# shades_v40.net
KiCad netlist of a schematic drawn in EAGLE
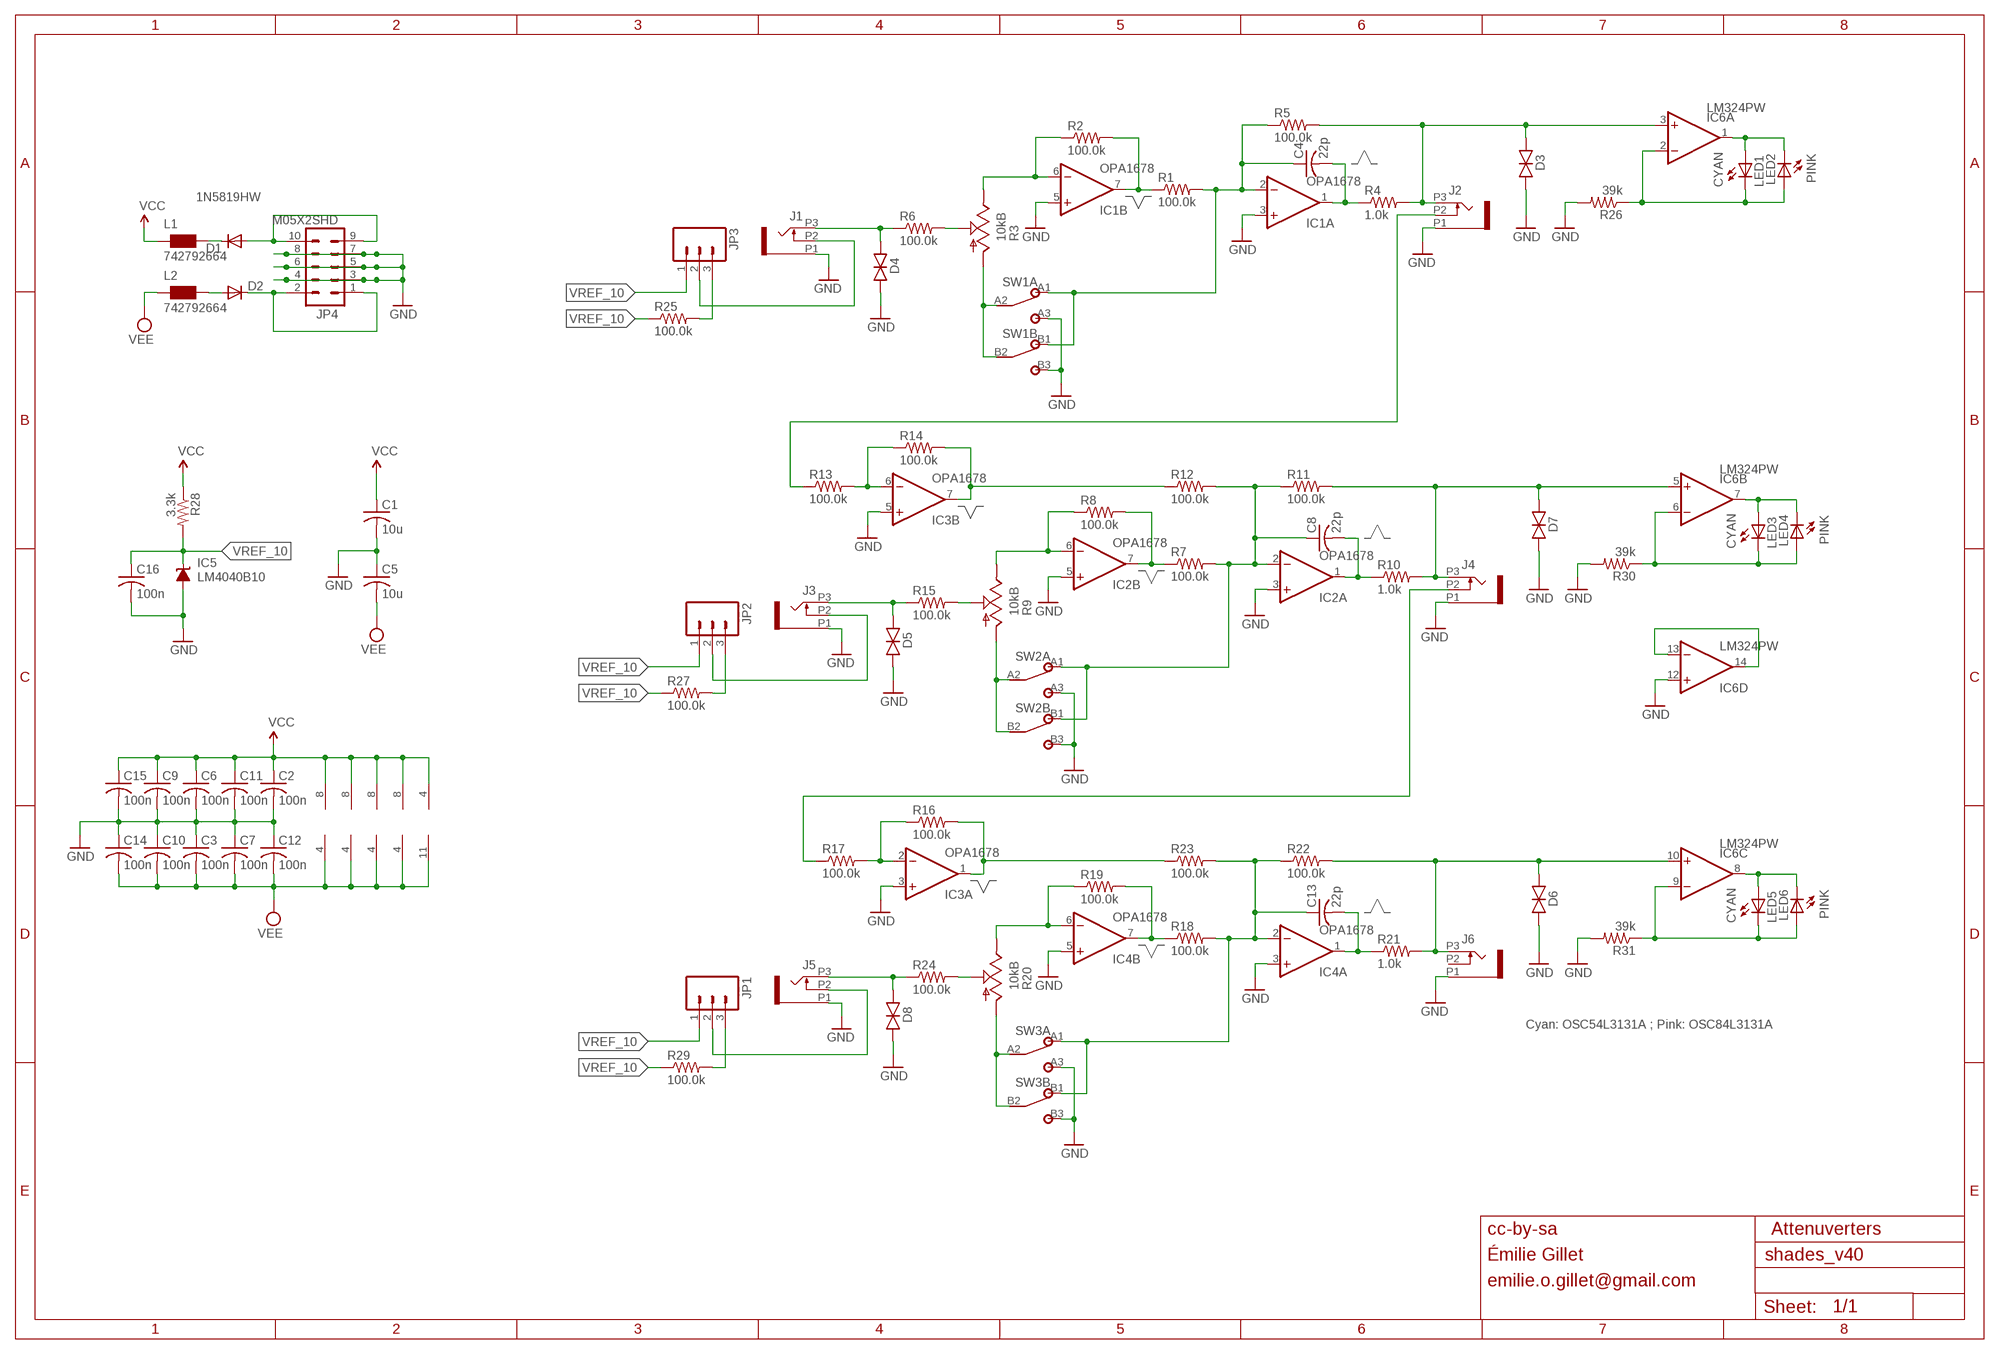
[diagram p0: schematic, sheet 1]

(export (version "E")
  (design (tool "Eeschema 10.0.6"))
  (components
    (comp (ref "C1")
      (value "10u")
      (footprint "eagle-import:C1210")
      (libsource (lib "eagle-import") (part "C-USC1210"))
    )
    (comp (ref "C2")
      (value "100n")
      (footprint "eagle-import:C0402")
      (libsource (lib "eagle-import") (part "C-USC0402"))
    )
    (comp (ref "C3")
      (value "100n")
      (footprint "eagle-import:C0402")
      (libsource (lib "eagle-import") (part "C-USC0402"))
    )
    (comp (ref "C4")
      (value "22p")
      (footprint "eagle-import:C0402")
      (libsource (lib "eagle-import") (part "C-USC0402"))
    )
    (comp (ref "C5")
      (value "10u")
      (footprint "eagle-import:C1210")
      (libsource (lib "eagle-import") (part "C-USC1210"))
    )
    (comp (ref "C6")
      (value "100n")
      (footprint "eagle-import:C0402")
      (libsource (lib "eagle-import") (part "C-USC0402"))
    )
    (comp (ref "C7")
      (value "100n")
      (footprint "eagle-import:C0402")
      (libsource (lib "eagle-import") (part "C-USC0402"))
    )
    (comp (ref "C8")
      (value "22p")
      (footprint "eagle-import:C0402")
      (libsource (lib "eagle-import") (part "C-USC0402"))
    )
    (comp (ref "C9")
      (value "100n")
      (footprint "eagle-import:C0402")
      (libsource (lib "eagle-import") (part "C-USC0402"))
    )
    (comp (ref "C10")
      (value "100n")
      (footprint "eagle-import:C0402")
      (libsource (lib "eagle-import") (part "C-USC0402"))
    )
    (comp (ref "C11")
      (value "100n")
      (footprint "eagle-import:C0402")
      (libsource (lib "eagle-import") (part "C-USC0402"))
    )
    (comp (ref "C12")
      (value "100n")
      (footprint "eagle-import:C0402")
      (libsource (lib "eagle-import") (part "C-USC0402"))
    )
    (comp (ref "C13")
      (value "22p")
      (footprint "eagle-import:C0402")
      (libsource (lib "eagle-import") (part "C-USC0402"))
    )
    (comp (ref "C14")
      (value "100n")
      (footprint "eagle-import:C0402")
      (libsource (lib "eagle-import") (part "C-USC0402"))
    )
    (comp (ref "C15")
      (value "100n")
      (footprint "eagle-import:C0402")
      (libsource (lib "eagle-import") (part "C-USC0402"))
    )
    (comp (ref "C16")
      (value "100n")
      (footprint "eagle-import:C0402")
      (libsource (lib "eagle-import") (part "C-USC0402"))
    )
    (comp (ref "D1")
      (value "1N5819HW")
      (footprint "eagle-import:SOD123")
      (libsource (lib "eagle-import") (part "DIODE-SOD123"))
    )
    (comp (ref "D2")
      (value "1N5819HW")
      (footprint "eagle-import:SOD123")
      (libsource (lib "eagle-import") (part "DIODE-SOD123"))
    )
    (comp (ref "D3")
      (value "TVS")
      (footprint "eagle-import:0603")
      (libsource (lib "eagle-import") (part "TVS"))
    )
    (comp (ref "D4")
      (value "TVS")
      (footprint "eagle-import:0603")
      (libsource (lib "eagle-import") (part "TVS"))
    )
    (comp (ref "D5")
      (value "TVS")
      (footprint "eagle-import:0603")
      (libsource (lib "eagle-import") (part "TVS"))
    )
    (comp (ref "D6")
      (value "TVS")
      (footprint "eagle-import:0603")
      (libsource (lib "eagle-import") (part "TVS"))
    )
    (comp (ref "D7")
      (value "TVS")
      (footprint "eagle-import:0603")
      (libsource (lib "eagle-import") (part "TVS"))
    )
    (comp (ref "D8")
      (value "TVS")
      (footprint "eagle-import:0603")
      (libsource (lib "eagle-import") (part "TVS"))
    )
    (comp (ref "IC1")
      (value "OPA1678")
      (footprint "eagle-import:VSSOP8")
      (libsource (lib "eagle-import") (part "OPA1678DGK"))
    )
    (comp (ref "IC2")
      (value "OPA1678")
      (footprint "eagle-import:VSSOP8")
      (libsource (lib "eagle-import") (part "OPA1678DGK"))
    )
    (comp (ref "IC3")
      (value "OPA1678")
      (footprint "eagle-import:VSSOP8")
      (libsource (lib "eagle-import") (part "OPA1678DGK"))
    )
    (comp (ref "IC4")
      (value "OPA1678")
      (footprint "eagle-import:VSSOP8")
      (libsource (lib "eagle-import") (part "OPA1678DGK"))
    )
    (comp (ref "IC5")
      (value "LM4040B10")
      (footprint "eagle-import:DBZ_R-PDSO-G3")
      (libsource (lib "eagle-import") (part "LM4041DBZB12"))
    )
    (comp (ref "IC6")
      (value "LM324PW")
      (footprint "eagle-import:TSSOP14_065")
      (libsource (lib "eagle-import") (part "TL074PW"))
    )
    (comp (ref "J1")
      (value "PJ301_THONKICONNTME")
      (footprint "eagle-import:WQP_PJ_301M_TME")
      (libsource (lib "eagle-import") (part "PJ301_THONKICONNTME"))
    )
    (comp (ref "J2")
      (value "PJ301_THONKICONNTME")
      (footprint "eagle-import:WQP_PJ_301M_TME")
      (libsource (lib "eagle-import") (part "PJ301_THONKICONNTME"))
    )
    (comp (ref "J3")
      (value "PJ301_THONKICONNTME")
      (footprint "eagle-import:WQP_PJ_301M_TME")
      (libsource (lib "eagle-import") (part "PJ301_THONKICONNTME"))
    )
    (comp (ref "J4")
      (value "PJ301_THONKICONNTME")
      (footprint "eagle-import:WQP_PJ_301M_TME")
      (libsource (lib "eagle-import") (part "PJ301_THONKICONNTME"))
    )
    (comp (ref "J5")
      (value "PJ301_THONKICONNTME")
      (footprint "eagle-import:WQP_PJ_301M_TME")
      (libsource (lib "eagle-import") (part "PJ301_THONKICONNTME"))
    )
    (comp (ref "J6")
      (value "PJ301_THONKICONNTME")
      (footprint "eagle-import:WQP_PJ_301M_TME")
      (libsource (lib "eagle-import") (part "PJ301_THONKICONNTME"))
    )
    (comp (ref "JP1")
      (value "M03PTH")
      (footprint "eagle-import:1X03")
      (libsource (lib "eagle-import") (part "M03PTH"))
    )
    (comp (ref "JP2")
      (value "M03PTH")
      (footprint "eagle-import:1X03")
      (libsource (lib "eagle-import") (part "M03PTH"))
    )
    (comp (ref "JP3")
      (value "M03PTH")
      (footprint "eagle-import:1X03")
      (libsource (lib "eagle-import") (part "M03PTH"))
    )
    (comp (ref "JP4")
      (value "M05X2SHD")
      (footprint "eagle-import:2X5-SHROUDED")
      (libsource (lib "eagle-import") (part "M05X2SHD"))
    )
    (comp (ref "L1")
      (value "742792664")
      (footprint "eagle-import:0603")
      (libsource (lib "eagle-import") (part "WE-CBF_0603"))
    )
    (comp (ref "L2")
      (value "742792664")
      (footprint "eagle-import:0603")
      (libsource (lib "eagle-import") (part "WE-CBF_0603"))
    )
    (comp (ref "LED1")
      (value "CYAN")
      (footprint "eagle-import:LED3MM")
      (libsource (lib "eagle-import") (part "LED3MM"))
    )
    (comp (ref "LED2")
      (value "PINK")
      (footprint "eagle-import:LED3MM")
      (libsource (lib "eagle-import") (part "LED3MM"))
    )
    (comp (ref "LED3")
      (value "CYAN")
      (footprint "eagle-import:LED3MM")
      (libsource (lib "eagle-import") (part "LED3MM"))
    )
    (comp (ref "LED4")
      (value "PINK")
      (footprint "eagle-import:LED3MM")
      (libsource (lib "eagle-import") (part "LED3MM"))
    )
    (comp (ref "LED5")
      (value "CYAN")
      (footprint "eagle-import:LED3MM")
      (libsource (lib "eagle-import") (part "LED3MM"))
    )
    (comp (ref "LED6")
      (value "PINK")
      (footprint "eagle-import:LED3MM")
      (libsource (lib "eagle-import") (part "LED3MM"))
    )
    (comp (ref "R1")
      (value "100.0k")
      (footprint "eagle-import:R0402")
      (libsource (lib "eagle-import") (part "R-US_R0402"))
    )
    (comp (ref "R2")
      (value "100.0k")
      (footprint "eagle-import:R0402")
      (libsource (lib "eagle-import") (part "R-US_R0402"))
    )
    (comp (ref "R3")
      (value "10kB")
      (footprint "eagle-import:ALPS_POT_VERTICAL_PS")
      (libsource (lib "eagle-import") (part "POT_USVERTICAL_PS"))
    )
    (comp (ref "R4")
      (value "1.0k")
      (footprint "eagle-import:R0603")
      (libsource (lib "eagle-import") (part "R-US_R0603"))
    )
    (comp (ref "R5")
      (value "100.0k")
      (footprint "eagle-import:R0402")
      (libsource (lib "eagle-import") (part "R-US_R0402"))
    )
    (comp (ref "R6")
      (value "100.0k")
      (footprint "eagle-import:R0402")
      (libsource (lib "eagle-import") (part "R-US_R0402"))
    )
    (comp (ref "R7")
      (value "100.0k")
      (footprint "eagle-import:R0402")
      (libsource (lib "eagle-import") (part "R-US_R0402"))
    )
    (comp (ref "R8")
      (value "100.0k")
      (footprint "eagle-import:R0402")
      (libsource (lib "eagle-import") (part "R-US_R0402"))
    )
    (comp (ref "R9")
      (value "10kB")
      (footprint "eagle-import:ALPS_POT_VERTICAL_PS")
      (libsource (lib "eagle-import") (part "POT_USVERTICAL_PS"))
    )
    (comp (ref "R10")
      (value "1.0k")
      (footprint "eagle-import:R0603")
      (libsource (lib "eagle-import") (part "R-US_R0603"))
    )
    (comp (ref "R11")
      (value "100.0k")
      (footprint "eagle-import:R0402")
      (libsource (lib "eagle-import") (part "R-US_R0402"))
    )
    (comp (ref "R12")
      (value "100.0k")
      (footprint "eagle-import:R0402")
      (libsource (lib "eagle-import") (part "R-US_R0402"))
    )
    (comp (ref "R13")
      (value "100.0k")
      (footprint "eagle-import:R0402")
      (libsource (lib "eagle-import") (part "R-US_R0402"))
    )
    (comp (ref "R14")
      (value "100.0k")
      (footprint "eagle-import:R0402")
      (libsource (lib "eagle-import") (part "R-US_R0402"))
    )
    (comp (ref "R15")
      (value "100.0k")
      (footprint "eagle-import:R0402")
      (libsource (lib "eagle-import") (part "R-US_R0402"))
    )
    (comp (ref "R16")
      (value "100.0k")
      (footprint "eagle-import:R0402")
      (libsource (lib "eagle-import") (part "R-US_R0402"))
    )
    (comp (ref "R17")
      (value "100.0k")
      (footprint "eagle-import:R0402")
      (libsource (lib "eagle-import") (part "R-US_R0402"))
    )
    (comp (ref "R18")
      (value "100.0k")
      (footprint "eagle-import:R0402")
      (libsource (lib "eagle-import") (part "R-US_R0402"))
    )
    (comp (ref "R19")
      (value "100.0k")
      (footprint "eagle-import:R0402")
      (libsource (lib "eagle-import") (part "R-US_R0402"))
    )
    (comp (ref "R20")
      (value "10kB")
      (footprint "eagle-import:ALPS_POT_VERTICAL_PS")
      (libsource (lib "eagle-import") (part "POT_USVERTICAL_PS"))
    )
    (comp (ref "R21")
      (value "1.0k")
      (footprint "eagle-import:R0603")
      (libsource (lib "eagle-import") (part "R-US_R0603"))
    )
    (comp (ref "R22")
      (value "100.0k")
      (footprint "eagle-import:R0402")
      (libsource (lib "eagle-import") (part "R-US_R0402"))
    )
    (comp (ref "R23")
      (value "100.0k")
      (footprint "eagle-import:R0402")
      (libsource (lib "eagle-import") (part "R-US_R0402"))
    )
    (comp (ref "R24")
      (value "100.0k")
      (footprint "eagle-import:R0402")
      (libsource (lib "eagle-import") (part "R-US_R0402"))
    )
    (comp (ref "R25")
      (value "100.0k")
      (footprint "eagle-import:R0402")
      (libsource (lib "eagle-import") (part "R-US_R0402"))
    )
    (comp (ref "R26")
      (value "39k")
      (footprint "eagle-import:R0402")
      (libsource (lib "eagle-import") (part "R-US_R0402"))
    )
    (comp (ref "R27")
      (value "100.0k")
      (footprint "eagle-import:R0402")
      (libsource (lib "eagle-import") (part "R-US_R0402"))
    )
    (comp (ref "R28")
      (value "3.3k")
      (footprint "eagle-import:R0402")
      (libsource (lib "eagle-import") (part "resistor_R-US_R0402"))
    )
    (comp (ref "R29")
      (value "100.0k")
      (footprint "eagle-import:R0402")
      (libsource (lib "eagle-import") (part "R-US_R0402"))
    )
    (comp (ref "R30")
      (value "39k")
      (footprint "eagle-import:R0402")
      (libsource (lib "eagle-import") (part "R-US_R0402"))
    )
    (comp (ref "R31")
      (value "39k")
      (footprint "eagle-import:R0402")
      (libsource (lib "eagle-import") (part "R-US_R0402"))
    )
    (comp (ref "SW1")
      (value "S-ON-ON-ONSS70070F-0202")
      (footprint "eagle-import:SS70070F-0202")
      (libsource (lib "eagle-import") (part "S-ON-ON-ONSS70070F-0202"))
    )
    (comp (ref "SW2")
      (value "S-ON-ON-ONSS70070F-0202")
      (footprint "eagle-import:SS70070F-0202")
      (libsource (lib "eagle-import") (part "S-ON-ON-ONSS70070F-0202"))
    )
    (comp (ref "SW3")
      (value "S-ON-ON-ONSS70070F-0202")
      (footprint "eagle-import:SS70070F-0202")
      (libsource (lib "eagle-import") (part "S-ON-ON-ONSS70070F-0202"))
    )
  )
  (nets
    (net (code "1") (name "GND") (class "Default")
      (node (ref "C1") (pin "2") (pinfunction "2_2") (pintype "passive"))
      (node (ref "C10") (pin "1") (pinfunction "1_1") (pintype "passive"))
      (node (ref "C11") (pin "2") (pinfunction "2_2") (pintype "passive"))
      (node (ref "C12") (pin "1") (pinfunction "1_1") (pintype "passive"))
      (node (ref "C14") (pin "1") (pinfunction "1_1") (pintype "passive"))
      (node (ref "C15") (pin "2") (pinfunction "2_2") (pintype "passive"))
      (node (ref "C16") (pin "2") (pinfunction "2_2") (pintype "passive"))
      (node (ref "C2") (pin "2") (pinfunction "2_2") (pintype "passive"))
      (node (ref "C3") (pin "1") (pinfunction "1_1") (pintype "passive"))
      (node (ref "C5") (pin "1") (pinfunction "1_1") (pintype "passive"))
      (node (ref "C6") (pin "2") (pinfunction "2_2") (pintype "passive"))
      (node (ref "C7") (pin "1") (pinfunction "1_1") (pintype "passive"))
      (node (ref "C9") (pin "2") (pinfunction "2_2") (pintype "passive"))
      (node (ref "D3") (pin "1") (pinfunction "A_1") (pintype "passive"))
      (node (ref "D4") (pin "1") (pinfunction "A_1") (pintype "passive"))
      (node (ref "D5") (pin "1") (pinfunction "A_1") (pintype "passive"))
      (node (ref "D6") (pin "1") (pinfunction "A_1") (pintype "passive"))
      (node (ref "D7") (pin "1") (pinfunction "A_1") (pintype "passive"))
      (node (ref "D8") (pin "1") (pinfunction "A_1") (pintype "passive"))
      (node (ref "IC1") (pin "3") (pinfunction "+IN_3") (pintype "input"))
      (node (ref "IC1") (pin "5") (pinfunction "+IN_5") (pintype "input"))
      (node (ref "IC2") (pin "3") (pinfunction "+IN_3") (pintype "input"))
      (node (ref "IC2") (pin "5") (pinfunction "+IN_5") (pintype "input"))
      (node (ref "IC3") (pin "3") (pinfunction "+IN_3") (pintype "input"))
      (node (ref "IC3") (pin "5") (pinfunction "+IN_5") (pintype "input"))
      (node (ref "IC4") (pin "3") (pinfunction "+IN_3") (pintype "input"))
      (node (ref "IC4") (pin "5") (pinfunction "+IN_5") (pintype "input"))
      (node (ref "IC5") (pin "2") (pinfunction "A_2") (pintype "passive"))
      (node (ref "IC6") (pin "12") (pinfunction "+IN_12") (pintype "input"))
      (node (ref "J1") (pin "P1") (pinfunction "1_P1") (pintype "passive"))
      (node (ref "J2") (pin "P1") (pinfunction "1_P1") (pintype "passive"))
      (node (ref "J3") (pin "P1") (pinfunction "1_P1") (pintype "passive"))
      (node (ref "J4") (pin "P1") (pinfunction "1_P1") (pintype "passive"))
      (node (ref "J5") (pin "P1") (pinfunction "1_P1") (pintype "passive"))
      (node (ref "J6") (pin "P1") (pinfunction "1_P1") (pintype "passive"))
      (node (ref "JP4") (pin "3") (pinfunction "3_3") (pintype "passive"))
      (node (ref "JP4") (pin "4") (pinfunction "4_4") (pintype "passive"))
      (node (ref "JP4") (pin "5") (pinfunction "5_5") (pintype "passive"))
      (node (ref "JP4") (pin "6") (pinfunction "6_6") (pintype "passive"))
      (node (ref "JP4") (pin "7") (pinfunction "7_7") (pintype "passive"))
      (node (ref "JP4") (pin "8") (pinfunction "8_8") (pintype "passive"))
      (node (ref "R26") (pin "2") (pinfunction "2_2") (pintype "passive"))
      (node (ref "R30") (pin "2") (pinfunction "2_2") (pintype "passive"))
      (node (ref "R31") (pin "2") (pinfunction "2_2") (pintype "passive"))
      (node (ref "SW1") (pin "A3") (pinfunction "3_A3") (pintype "passive"))
      (node (ref "SW1") (pin "B3") (pinfunction "3_B3") (pintype "passive"))
      (node (ref "SW2") (pin "A3") (pinfunction "3_A3") (pintype "passive"))
      (node (ref "SW2") (pin "B3") (pinfunction "3_B3") (pintype "passive"))
      (node (ref "SW3") (pin "A3") (pinfunction "3_A3") (pintype "passive"))
      (node (ref "SW3") (pin "B3") (pinfunction "3_B3") (pintype "passive"))
    )
    (net (code "2") (name "Net-(D1-PadA)") (class "Default")
      (node (ref "D1") (pin "A") (pinfunction "A_A") (pintype "passive"))
      (node (ref "JP4") (pin "10") (pinfunction "10_10") (pintype "passive"))
      (node (ref "JP4") (pin "9") (pinfunction "9_9") (pintype "passive"))
    )
    (net (code "3") (name "Net-(D1-PadC)") (class "Default")
      (node (ref "D1") (pin "C") (pinfunction "C_C") (pintype "passive"))
      (node (ref "L1") (pin "2") (pinfunction "2_2") (pintype "passive"))
    )
    (net (code "4") (name "Net-(D2-PadA)") (class "Default")
      (node (ref "D2") (pin "A") (pinfunction "A_A") (pintype "passive"))
      (node (ref "L2") (pin "2") (pinfunction "2_2") (pintype "passive"))
    )
    (net (code "5") (name "Net-(D2-PadC)") (class "Default")
      (node (ref "D2") (pin "C") (pinfunction "C_C") (pintype "passive"))
      (node (ref "JP4") (pin "1") (pinfunction "1_1") (pintype "passive"))
      (node (ref "JP4") (pin "2") (pinfunction "2_2") (pintype "passive"))
    )
    (net (code "6") (name "Net-(D3-C)") (class "Default")
      (node (ref "D3") (pin "2") (pinfunction "C_2") (pintype "passive"))
      (node (ref "IC6") (pin "3") (pinfunction "+IN_3") (pintype "input"))
      (node (ref "J2") (pin "P3") (pinfunction "3_P3") (pintype "passive"))
      (node (ref "R4") (pin "2") (pinfunction "2_2") (pintype "passive"))
      (node (ref "R5") (pin "2") (pinfunction "2_2") (pintype "passive"))
    )
    (net (code "7") (name "Net-(D4-C)") (class "Default")
      (node (ref "D4") (pin "2") (pinfunction "C_2") (pintype "passive"))
      (node (ref "J1") (pin "P3") (pinfunction "3_P3") (pintype "passive"))
      (node (ref "R6") (pin "1") (pinfunction "1_1") (pintype "passive"))
    )
    (net (code "8") (name "Net-(D5-C)") (class "Default")
      (node (ref "D5") (pin "2") (pinfunction "C_2") (pintype "passive"))
      (node (ref "J3") (pin "P3") (pinfunction "3_P3") (pintype "passive"))
      (node (ref "R15") (pin "1") (pinfunction "1_1") (pintype "passive"))
    )
    (net (code "9") (name "Net-(D6-C)") (class "Default")
      (node (ref "D6") (pin "2") (pinfunction "C_2") (pintype "passive"))
      (node (ref "IC6") (pin "10") (pinfunction "+IN_10") (pintype "input"))
      (node (ref "J6") (pin "P3") (pinfunction "3_P3") (pintype "passive"))
      (node (ref "R21") (pin "2") (pinfunction "2_2") (pintype "passive"))
      (node (ref "R22") (pin "2") (pinfunction "2_2") (pintype "passive"))
    )
    (net (code "10") (name "Net-(D7-C)") (class "Default")
      (node (ref "D7") (pin "2") (pinfunction "C_2") (pintype "passive"))
      (node (ref "IC6") (pin "5") (pinfunction "+IN_5") (pintype "input"))
      (node (ref "J4") (pin "P3") (pinfunction "3_P3") (pintype "passive"))
      (node (ref "R10") (pin "2") (pinfunction "2_2") (pintype "passive"))
      (node (ref "R11") (pin "2") (pinfunction "2_2") (pintype "passive"))
    )
    (net (code "11") (name "Net-(D8-C)") (class "Default")
      (node (ref "D8") (pin "2") (pinfunction "C_2") (pintype "passive"))
      (node (ref "J5") (pin "P3") (pinfunction "3_P3") (pintype "passive"))
      (node (ref "R24") (pin "1") (pinfunction "1_1") (pintype "passive"))
    )
    (net (code "12") (name "Net-(IC1A--IN)") (class "Default")
      (node (ref "C4") (pin "1") (pinfunction "1_1") (pintype "passive"))
      (node (ref "IC1") (pin "2") (pinfunction "-IN_2") (pintype "input"))
      (node (ref "R1") (pin "2") (pinfunction "2_2") (pintype "passive"))
      (node (ref "R5") (pin "1") (pinfunction "1_1") (pintype "passive"))
      (node (ref "SW1") (pin "A1") (pinfunction "1_A1") (pintype "passive"))
      (node (ref "SW1") (pin "B1") (pinfunction "1_B1") (pintype "passive"))
    )
    (net (code "13") (name "Net-(IC1A-OUT)") (class "Default")
      (node (ref "C4") (pin "2") (pinfunction "2_2") (pintype "passive"))
      (node (ref "IC1") (pin "1") (pinfunction "OUT_1") (pintype "output"))
      (node (ref "R4") (pin "1") (pinfunction "1_1") (pintype "passive"))
    )
    (net (code "14") (name "Net-(IC1B--IN)") (class "Default")
      (node (ref "IC1") (pin "6") (pinfunction "-IN_6") (pintype "input"))
      (node (ref "R2") (pin "1") (pinfunction "1_1") (pintype "passive"))
      (node (ref "R3") (pin "P$1") (pinfunction "E_P$1") (pintype "passive"))
    )
    (net (code "15") (name "Net-(IC1B-OUT)") (class "Default")
      (node (ref "IC1") (pin "7") (pinfunction "OUT_7") (pintype "output"))
      (node (ref "R1") (pin "1") (pinfunction "1_1") (pintype "passive"))
      (node (ref "R2") (pin "2") (pinfunction "2_2") (pintype "passive"))
    )
    (net (code "16") (name "Net-(IC2A--IN)") (class "Default")
      (node (ref "C8") (pin "1") (pinfunction "1_1") (pintype "passive"))
      (node (ref "IC2") (pin "2") (pinfunction "-IN_2") (pintype "input"))
      (node (ref "R11") (pin "1") (pinfunction "1_1") (pintype "passive"))
      (node (ref "R12") (pin "2") (pinfunction "2_2") (pintype "passive"))
      (node (ref "R7") (pin "2") (pinfunction "2_2") (pintype "passive"))
      (node (ref "SW2") (pin "A1") (pinfunction "1_A1") (pintype "passive"))
      (node (ref "SW2") (pin "B1") (pinfunction "1_B1") (pintype "passive"))
    )
    (net (code "17") (name "Net-(IC2A-OUT)") (class "Default")
      (node (ref "C8") (pin "2") (pinfunction "2_2") (pintype "passive"))
      (node (ref "IC2") (pin "1") (pinfunction "OUT_1") (pintype "output"))
      (node (ref "R10") (pin "1") (pinfunction "1_1") (pintype "passive"))
    )
    (net (code "18") (name "Net-(IC2B--IN)") (class "Default")
      (node (ref "IC2") (pin "6") (pinfunction "-IN_6") (pintype "input"))
      (node (ref "R8") (pin "1") (pinfunction "1_1") (pintype "passive"))
      (node (ref "R9") (pin "P$1") (pinfunction "E_P$1") (pintype "passive"))
    )
    (net (code "19") (name "Net-(IC2B-OUT)") (class "Default")
      (node (ref "IC2") (pin "7") (pinfunction "OUT_7") (pintype "output"))
      (node (ref "R7") (pin "1") (pinfunction "1_1") (pintype "passive"))
      (node (ref "R8") (pin "2") (pinfunction "2_2") (pintype "passive"))
    )
    (net (code "20") (name "Net-(IC3A--IN)") (class "Default")
      (node (ref "IC3") (pin "2") (pinfunction "-IN_2") (pintype "input"))
      (node (ref "R16") (pin "1") (pinfunction "1_1") (pintype "passive"))
      (node (ref "R17") (pin "2") (pinfunction "2_2") (pintype "passive"))
    )
    (net (code "21") (name "Net-(IC3A-OUT)") (class "Default")
      (node (ref "IC3") (pin "1") (pinfunction "OUT_1") (pintype "output"))
      (node (ref "R16") (pin "2") (pinfunction "2_2") (pintype "passive"))
      (node (ref "R23") (pin "1") (pinfunction "1_1") (pintype "passive"))
    )
    (net (code "22") (name "Net-(IC3B--IN)") (class "Default")
      (node (ref "IC3") (pin "6") (pinfunction "-IN_6") (pintype "input"))
      (node (ref "R13") (pin "2") (pinfunction "2_2") (pintype "passive"))
      (node (ref "R14") (pin "1") (pinfunction "1_1") (pintype "passive"))
    )
    (net (code "23") (name "Net-(IC3B-OUT)") (class "Default")
      (node (ref "IC3") (pin "7") (pinfunction "OUT_7") (pintype "output"))
      (node (ref "R12") (pin "1") (pinfunction "1_1") (pintype "passive"))
      (node (ref "R14") (pin "2") (pinfunction "2_2") (pintype "passive"))
    )
    (net (code "24") (name "Net-(IC4A--IN)") (class "Default")
      (node (ref "C13") (pin "1") (pinfunction "1_1") (pintype "passive"))
      (node (ref "IC4") (pin "2") (pinfunction "-IN_2") (pintype "input"))
      (node (ref "R18") (pin "2") (pinfunction "2_2") (pintype "passive"))
      (node (ref "R22") (pin "1") (pinfunction "1_1") (pintype "passive"))
      (node (ref "R23") (pin "2") (pinfunction "2_2") (pintype "passive"))
      (node (ref "SW3") (pin "A1") (pinfunction "1_A1") (pintype "passive"))
      (node (ref "SW3") (pin "B1") (pinfunction "1_B1") (pintype "passive"))
    )
    (net (code "25") (name "Net-(IC4A-OUT)") (class "Default")
      (node (ref "C13") (pin "2") (pinfunction "2_2") (pintype "passive"))
      (node (ref "IC4") (pin "1") (pinfunction "OUT_1") (pintype "output"))
      (node (ref "R21") (pin "1") (pinfunction "1_1") (pintype "passive"))
    )
    (net (code "26") (name "Net-(IC4B--IN)") (class "Default")
      (node (ref "IC4") (pin "6") (pinfunction "-IN_6") (pintype "input"))
      (node (ref "R19") (pin "1") (pinfunction "1_1") (pintype "passive"))
      (node (ref "R20") (pin "P$1") (pinfunction "E_P$1") (pintype "passive"))
    )
    (net (code "27") (name "Net-(IC4B-OUT)") (class "Default")
      (node (ref "IC4") (pin "7") (pinfunction "OUT_7") (pintype "output"))
      (node (ref "R18") (pin "1") (pinfunction "1_1") (pintype "passive"))
      (node (ref "R19") (pin "2") (pinfunction "2_2") (pintype "passive"))
    )
    (net (code "28") (name "Net-(IC6A--IN)") (class "Default")
      (node (ref "IC6") (pin "2") (pinfunction "-IN_2") (pintype "input"))
      (node (ref "LED1") (pin "K") (pinfunction "C_K") (pintype "passive"))
      (node (ref "LED2") (pin "A") (pinfunction "A_A") (pintype "passive"))
      (node (ref "R26") (pin "1") (pinfunction "1_1") (pintype "passive"))
    )
    (net (code "29") (name "Net-(IC6A-OUT)") (class "Default")
      (node (ref "IC6") (pin "1") (pinfunction "OUT_1") (pintype "output"))
      (node (ref "LED1") (pin "A") (pinfunction "A_A") (pintype "passive"))
      (node (ref "LED2") (pin "K") (pinfunction "C_K") (pintype "passive"))
    )
    (net (code "30") (name "Net-(IC6B--IN)") (class "Default")
      (node (ref "IC6") (pin "6") (pinfunction "-IN_6") (pintype "input"))
      (node (ref "LED3") (pin "K") (pinfunction "C_K") (pintype "passive"))
      (node (ref "LED4") (pin "A") (pinfunction "A_A") (pintype "passive"))
      (node (ref "R30") (pin "1") (pinfunction "1_1") (pintype "passive"))
    )
    (net (code "31") (name "Net-(IC6B-OUT)") (class "Default")
      (node (ref "IC6") (pin "7") (pinfunction "OUT_7") (pintype "output"))
      (node (ref "LED3") (pin "A") (pinfunction "A_A") (pintype "passive"))
      (node (ref "LED4") (pin "K") (pinfunction "C_K") (pintype "passive"))
    )
    (net (code "32") (name "Net-(IC6C--IN)") (class "Default")
      (node (ref "IC6") (pin "9") (pinfunction "-IN_9") (pintype "input"))
      (node (ref "LED5") (pin "K") (pinfunction "C_K") (pintype "passive"))
      (node (ref "LED6") (pin "A") (pinfunction "A_A") (pintype "passive"))
      (node (ref "R31") (pin "1") (pinfunction "1_1") (pintype "passive"))
    )
    (net (code "33") (name "Net-(IC6C-OUT)") (class "Default")
      (node (ref "IC6") (pin "8") (pinfunction "OUT_8") (pintype "output"))
      (node (ref "LED5") (pin "A") (pinfunction "A_A") (pintype "passive"))
      (node (ref "LED6") (pin "K") (pinfunction "C_K") (pintype "passive"))
    )
    (net (code "34") (name "Net-(IC6D--IN)") (class "Default")
      (node (ref "IC6") (pin "13") (pinfunction "-IN_13") (pintype "input"))
      (node (ref "IC6") (pin "14") (pinfunction "OUT_14") (pintype "output"))
    )
    (net (code "35") (name "Net-(J1-2)") (class "Default")
      (node (ref "J1") (pin "P2") (pinfunction "2_P2") (pintype "passive"))
      (node (ref "JP3") (pin "2") (pinfunction "2_2") (pintype "passive"))
    )
    (net (code "36") (name "Net-(J2-2)") (class "Default")
      (node (ref "J2") (pin "P2") (pinfunction "2_P2") (pintype "passive"))
      (node (ref "R13") (pin "1") (pinfunction "1_1") (pintype "passive"))
    )
    (net (code "37") (name "Net-(J3-2)") (class "Default")
      (node (ref "J3") (pin "P2") (pinfunction "2_P2") (pintype "passive"))
      (node (ref "JP2") (pin "2") (pinfunction "2_2") (pintype "passive"))
    )
    (net (code "38") (name "Net-(J4-2)") (class "Default")
      (node (ref "J4") (pin "P2") (pinfunction "2_P2") (pintype "passive"))
      (node (ref "R17") (pin "1") (pinfunction "1_1") (pintype "passive"))
    )
    (net (code "39") (name "Net-(J5-2)") (class "Default")
      (node (ref "J5") (pin "P2") (pinfunction "2_P2") (pintype "passive"))
      (node (ref "JP1") (pin "2") (pinfunction "2_2") (pintype "passive"))
    )
    (net (code "40") (name "Net-(JP1-Pad3)") (class "Default")
      (node (ref "JP1") (pin "3") (pinfunction "3_3") (pintype "passive"))
      (node (ref "R29") (pin "2") (pinfunction "2_2") (pintype "passive"))
    )
    (net (code "41") (name "Net-(JP2-Pad3)") (class "Default")
      (node (ref "JP2") (pin "3") (pinfunction "3_3") (pintype "passive"))
      (node (ref "R27") (pin "2") (pinfunction "2_2") (pintype "passive"))
    )
    (net (code "42") (name "Net-(JP3-Pad3)") (class "Default")
      (node (ref "JP3") (pin "3") (pinfunction "3_3") (pintype "passive"))
      (node (ref "R25") (pin "2") (pinfunction "2_2") (pintype "passive"))
    )
    (net (code "43") (name "Net-(R3-A)") (class "Default")
      (node (ref "R3") (pin "P$3") (pinfunction "A_P$3") (pintype "passive"))
      (node (ref "SW1") (pin "A2") (pinfunction "2_A2") (pintype "passive"))
      (node (ref "SW1") (pin "B2") (pinfunction "2_B2") (pintype "passive"))
    )
    (net (code "44") (name "Net-(R3-S)") (class "Default")
      (node (ref "R3") (pin "P$2") (pinfunction "S_P$2") (pintype "passive"))
      (node (ref "R6") (pin "2") (pinfunction "2_2") (pintype "passive"))
    )
    (net (code "45") (name "Net-(R9-A)") (class "Default")
      (node (ref "R9") (pin "P$3") (pinfunction "A_P$3") (pintype "passive"))
      (node (ref "SW2") (pin "A2") (pinfunction "2_A2") (pintype "passive"))
      (node (ref "SW2") (pin "B2") (pinfunction "2_B2") (pintype "passive"))
    )
    (net (code "46") (name "Net-(R9-S)") (class "Default")
      (node (ref "R15") (pin "2") (pinfunction "2_2") (pintype "passive"))
      (node (ref "R9") (pin "P$2") (pinfunction "S_P$2") (pintype "passive"))
    )
    (net (code "47") (name "Net-(R20-A)") (class "Default")
      (node (ref "R20") (pin "P$3") (pinfunction "A_P$3") (pintype "passive"))
      (node (ref "SW3") (pin "A2") (pinfunction "2_A2") (pintype "passive"))
      (node (ref "SW3") (pin "B2") (pinfunction "2_B2") (pintype "passive"))
    )
    (net (code "48") (name "Net-(R20-S)") (class "Default")
      (node (ref "R20") (pin "P$2") (pinfunction "S_P$2") (pintype "passive"))
      (node (ref "R24") (pin "2") (pinfunction "2_2") (pintype "passive"))
    )
    (net (code "49") (name "VCC") (class "Default")
      (node (ref "C1") (pin "1") (pinfunction "1_1") (pintype "passive"))
      (node (ref "C11") (pin "1") (pinfunction "1_1") (pintype "passive"))
      (node (ref "C15") (pin "1") (pinfunction "1_1") (pintype "passive"))
      (node (ref "C2") (pin "1") (pinfunction "1_1") (pintype "passive"))
      (node (ref "C6") (pin "1") (pinfunction "1_1") (pintype "passive"))
      (node (ref "C9") (pin "1") (pinfunction "1_1") (pintype "passive"))
      (node (ref "IC1") (pin "8") (pinfunction "V+_8") (pintype "power_in"))
      (node (ref "IC2") (pin "8") (pinfunction "V+_8") (pintype "power_in"))
      (node (ref "IC3") (pin "8") (pinfunction "V+_8") (pintype "power_in"))
      (node (ref "IC4") (pin "8") (pinfunction "V+_8") (pintype "power_in"))
      (node (ref "IC6") (pin "4") (pinfunction "V+_4") (pintype "power_in"))
      (node (ref "L1") (pin "1") (pinfunction "1_1") (pintype "passive"))
      (node (ref "R28") (pin "1") (pinfunction "1_1") (pintype "passive"))
    )
    (net (code "50") (name "VEE") (class "Default")
      (node (ref "C10") (pin "2") (pinfunction "2_2") (pintype "passive"))
      (node (ref "C12") (pin "2") (pinfunction "2_2") (pintype "passive"))
      (node (ref "C14") (pin "2") (pinfunction "2_2") (pintype "passive"))
      (node (ref "C3") (pin "2") (pinfunction "2_2") (pintype "passive"))
      (node (ref "C5") (pin "2") (pinfunction "2_2") (pintype "passive"))
      (node (ref "C7") (pin "2") (pinfunction "2_2") (pintype "passive"))
      (node (ref "IC1") (pin "4") (pinfunction "V-_4") (pintype "power_in"))
      (node (ref "IC2") (pin "4") (pinfunction "V-_4") (pintype "power_in"))
      (node (ref "IC3") (pin "4") (pinfunction "V-_4") (pintype "power_in"))
      (node (ref "IC4") (pin "4") (pinfunction "V-_4") (pintype "power_in"))
      (node (ref "IC6") (pin "11") (pinfunction "V-_11") (pintype "power_in"))
      (node (ref "L2") (pin "1") (pinfunction "1_1") (pintype "passive"))
    )
    (net (code "51") (name "VREF_10") (class "Default")
      (node (ref "C16") (pin "1") (pinfunction "1_1") (pintype "passive"))
      (node (ref "IC5") (pin "1") (pinfunction "C_1") (pintype "passive"))
      (node (ref "JP1") (pin "1") (pinfunction "1_1") (pintype "passive"))
      (node (ref "JP2") (pin "1") (pinfunction "1_1") (pintype "passive"))
      (node (ref "JP3") (pin "1") (pinfunction "1_1") (pintype "passive"))
      (node (ref "R25") (pin "1") (pinfunction "1_1") (pintype "passive"))
      (node (ref "R27") (pin "1") (pinfunction "1_1") (pintype "passive"))
      (node (ref "R28") (pin "2") (pinfunction "2_2") (pintype "passive"))
      (node (ref "R29") (pin "1") (pinfunction "1_1") (pintype "passive"))
    )
    (net (code "52") (name "unconnected-(J6-2-PadP2)") (class "Default")
      (node (ref "J6") (pin "P2") (pinfunction "2_P2") (pintype "passive"))
    )
  )
)
